# PMOD_PMOD_connector.net
KiCad netlist of a schematic drawn in Altium Designer
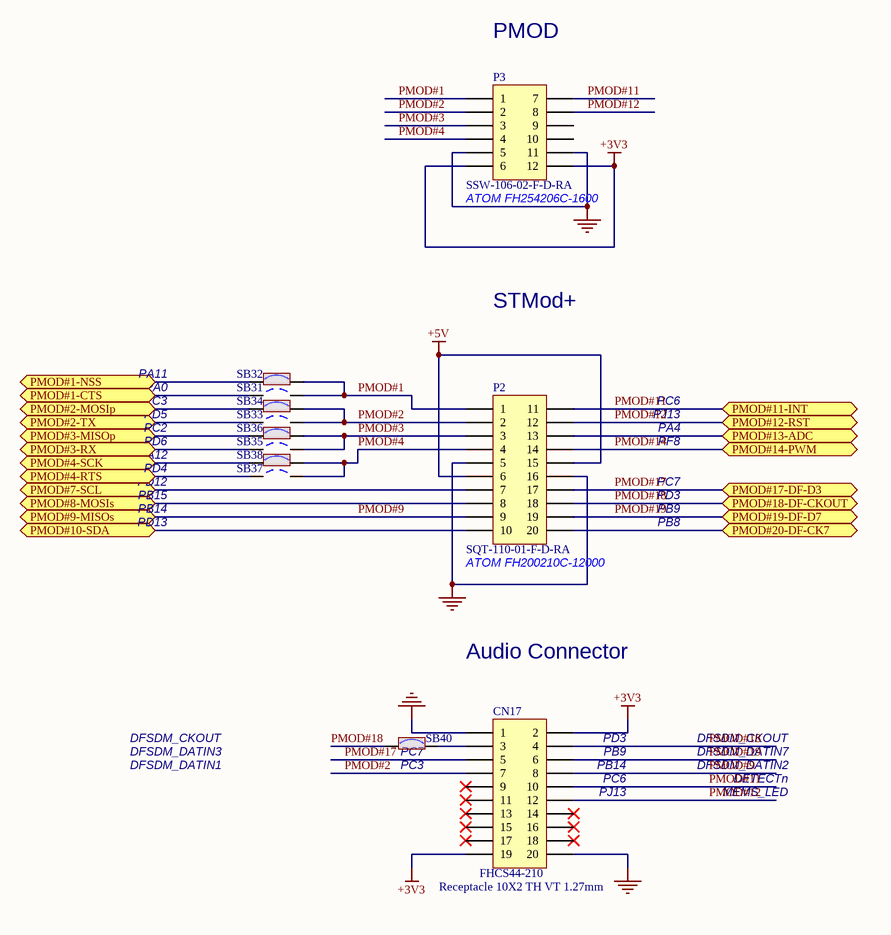
[diagram p0: PMOD_PMOD+ connector .SchDoc]

(export (version "E")
  (design (tool "Eeschema 10.0.6"))
  (components
    (comp (ref "CN17")
      (value "Receptacle 10X2 TH VT 1.27mm")
      (footprint "MODULE_20TH_48X29")
      (description "20 Position Receptacle Connector 0.050\" (1.27mm) Through Hole Vertical Mount")
      (fields (field (name "ORDER_CODE") "FHCS44-210"))
      (libsource (lib "MCD_TEMP_PCH") (part "Receptacle 10X2 TH VT 1.27mm"))
    )
    (comp (ref "P2")
      (value "SQT-110-01-F-D-RA")
      (footprint "SQT-110-01-F-D-RA")
      (description "Header, 10-Pin, Dual row")
      (fields (field (name "PUBLISHER") "Altium Limited"))
      (libsource (lib "Miscellaneous Connectors") (part "Header 10X2A"))
    )
    (comp (ref "P3")
      (value "SSW-106-02-F-D-RA")
      (footprint "SSW-106-02-F-D-RA")
      (description "Header, 6-Pin, Dual row")
      (fields (field (name "PUBLISHER") "Altium Limited"))
      (libsource (lib "Miscellaneous Connectors") (part "Header 6X2A"))
    )
    (comp (ref "SB31")
      (value "Solder Bridge OFF")
      (footprint "SB_0603")
      (libsource (lib "MCD_TOOLS") (part "SB_OFF"))
    )
    (comp (ref "SB32")
      (value "Solder Bridge ON")
      (footprint "SB_0603")
      (libsource (lib "MCD_TOOLS") (part "SB_ON"))
    )
    (comp (ref "SB33")
      (value "Solder Bridge OFF")
      (footprint "SB_0603")
      (libsource (lib "MCD_TOOLS") (part "SB_OFF"))
    )
    (comp (ref "SB34")
      (value "Solder Bridge ON")
      (footprint "SB_0603")
      (libsource (lib "MCD_TOOLS") (part "SB_ON"))
    )
    (comp (ref "SB35")
      (value "Solder Bridge OFF")
      (footprint "SB_0603")
      (libsource (lib "MCD_TOOLS") (part "SB_OFF"))
    )
    (comp (ref "SB36")
      (value "Solder Bridge ON")
      (footprint "SB_0603")
      (libsource (lib "MCD_TOOLS") (part "SB_ON"))
    )
    (comp (ref "SB37")
      (value "Solder Bridge OFF")
      (footprint "SB_0603")
      (libsource (lib "MCD_TOOLS") (part "SB_OFF"))
    )
    (comp (ref "SB38")
      (value "Solder Bridge ON")
      (footprint "SB_0603")
      (libsource (lib "MCD_TOOLS") (part "SB_ON"))
    )
    (comp (ref "SB40")
      (value "Solder Bridge ON")
      (footprint "SB_0603")
      (libsource (lib "MCD_TOOLS") (part "SB_ON"))
    )
  )
  (nets
    (net (code "1") (name "+3V3") (class "Default")
      (node (ref "CN17") (pin "19") (pinfunction "19_19") (pintype "passive"))
      (node (ref "CN17") (pin "2") (pinfunction "2_2") (pintype "passive"))
      (node (ref "P3") (pin "12") (pinfunction "12_12") (pintype "passive"))
      (node (ref "P3") (pin "6") (pinfunction "6_6") (pintype "passive"))
    )
    (net (code "2") (name "+5V") (class "Default")
      (node (ref "P2") (pin "15") (pinfunction "15_15") (pintype "passive"))
      (node (ref "P2") (pin "6") (pinfunction "6_6") (pintype "passive"))
    )
    (net (code "3") (name "/PMOD#1") (class "Default")
      (node (ref "P2") (pin "1") (pinfunction "1_1") (pintype "passive"))
      (node (ref "P3") (pin "1") (pinfunction "1_1") (pintype "passive"))
      (node (ref "SB31") (pin "2") (pinfunction "2_2") (pintype "passive"))
      (node (ref "SB32") (pin "2") (pinfunction "2_2") (pintype "passive"))
    )
    (net (code "4") (name "/PMOD#1-CTS") (class "Default")
      (node (ref "SB31") (pin "1") (pinfunction "1_1") (pintype "passive"))
    )
    (net (code "5") (name "/PMOD#1-NSS") (class "Default")
      (node (ref "SB32") (pin "1") (pinfunction "1_1") (pintype "passive"))
    )
    (net (code "6") (name "/PMOD#2") (class "Default")
      (node (ref "CN17") (pin "7") (pinfunction "7_7") (pintype "passive"))
      (node (ref "P2") (pin "2") (pinfunction "2_2") (pintype "passive"))
      (node (ref "P3") (pin "2") (pinfunction "2_2") (pintype "passive"))
      (node (ref "SB33") (pin "2") (pinfunction "2_2") (pintype "passive"))
      (node (ref "SB34") (pin "2") (pinfunction "2_2") (pintype "passive"))
    )
    (net (code "7") (name "/PMOD#2-MOSIp") (class "Default")
      (node (ref "SB34") (pin "1") (pinfunction "1_1") (pintype "passive"))
    )
    (net (code "8") (name "/PMOD#2-TX") (class "Default")
      (node (ref "SB33") (pin "1") (pinfunction "1_1") (pintype "passive"))
    )
    (net (code "9") (name "/PMOD#3") (class "Default")
      (node (ref "P2") (pin "3") (pinfunction "3_3") (pintype "passive"))
      (node (ref "P3") (pin "3") (pinfunction "3_3") (pintype "passive"))
      (node (ref "SB35") (pin "2") (pinfunction "2_2") (pintype "passive"))
      (node (ref "SB36") (pin "2") (pinfunction "2_2") (pintype "passive"))
    )
    (net (code "10") (name "/PMOD#3-MISOp") (class "Default")
      (node (ref "SB36") (pin "1") (pinfunction "1_1") (pintype "passive"))
    )
    (net (code "11") (name "/PMOD#3-RX") (class "Default")
      (node (ref "SB35") (pin "1") (pinfunction "1_1") (pintype "passive"))
    )
    (net (code "12") (name "/PMOD#4") (class "Default")
      (node (ref "P2") (pin "4") (pinfunction "4_4") (pintype "passive"))
      (node (ref "P3") (pin "4") (pinfunction "4_4") (pintype "passive"))
      (node (ref "SB37") (pin "2") (pinfunction "2_2") (pintype "passive"))
      (node (ref "SB38") (pin "2") (pinfunction "2_2") (pintype "passive"))
    )
    (net (code "13") (name "/PMOD#4-RTS") (class "Default")
      (node (ref "SB37") (pin "1") (pinfunction "1_1") (pintype "passive"))
    )
    (net (code "14") (name "/PMOD#4-SCK") (class "Default")
      (node (ref "SB38") (pin "1") (pinfunction "1_1") (pintype "passive"))
    )
    (net (code "15") (name "/PMOD#7-SCL") (class "Default")
      (node (ref "P2") (pin "7") (pinfunction "7_7") (pintype "passive"))
    )
    (net (code "16") (name "/PMOD#8-MOSIs") (class "Default")
      (node (ref "P2") (pin "8") (pinfunction "8_8") (pintype "passive"))
    )
    (net (code "17") (name "/PMOD#9") (class "Default")
      (node (ref "CN17") (pin "8") (pinfunction "8_8") (pintype "passive"))
      (node (ref "P2") (pin "9") (pinfunction "9_9") (pintype "passive"))
    )
    (net (code "18") (name "/PMOD#10-SDA") (class "Default")
      (node (ref "P2") (pin "10") (pinfunction "10_10") (pintype "passive"))
    )
    (net (code "19") (name "/PMOD#11") (class "Default")
      (node (ref "CN17") (pin "10") (pinfunction "10_10") (pintype "passive"))
      (node (ref "P2") (pin "11") (pinfunction "11_11") (pintype "passive"))
      (node (ref "P3") (pin "7") (pinfunction "7_7") (pintype "passive"))
    )
    (net (code "20") (name "/PMOD#12") (class "Default")
      (node (ref "CN17") (pin "12") (pinfunction "12_12") (pintype "passive"))
      (node (ref "P2") (pin "12") (pinfunction "12_12") (pintype "passive"))
      (node (ref "P3") (pin "8") (pinfunction "8_8") (pintype "passive"))
    )
    (net (code "21") (name "/PMOD#13-ADC") (class "Default")
      (node (ref "P2") (pin "13") (pinfunction "13_13") (pintype "passive"))
    )
    (net (code "22") (name "/PMOD#14") (class "Default")
      (node (ref "P2") (pin "14") (pinfunction "14_14") (pintype "passive"))
    )
    (net (code "23") (name "/PMOD#17") (class "Default")
      (node (ref "CN17") (pin "5") (pinfunction "5_5") (pintype "passive"))
      (node (ref "P2") (pin "17") (pinfunction "17_17") (pintype "passive"))
    )
    (net (code "24") (name "/PMOD#18") (class "Default")
      (node (ref "CN17") (pin "4") (pinfunction "4_4") (pintype "passive"))
      (node (ref "P2") (pin "18") (pinfunction "18_18") (pintype "passive"))
      (node (ref "SB40") (pin "1") (pinfunction "1_1") (pintype "passive"))
    )
    (net (code "25") (name "/PMOD#19") (class "Default")
      (node (ref "CN17") (pin "6") (pinfunction "6_6") (pintype "passive"))
      (node (ref "P2") (pin "19") (pinfunction "19_19") (pintype "passive"))
    )
    (net (code "26") (name "/PMOD#20-DF-CK7") (class "Default")
      (node (ref "P2") (pin "20") (pinfunction "20_20") (pintype "passive"))
    )
    (net (code "27") (name "GND") (class "Default")
      (node (ref "CN17") (pin "1") (pinfunction "1_1") (pintype "passive"))
      (node (ref "CN17") (pin "20") (pinfunction "20_20") (pintype "passive"))
      (node (ref "P2") (pin "16") (pinfunction "16_16") (pintype "passive"))
      (node (ref "P2") (pin "5") (pinfunction "5_5") (pintype "passive"))
      (node (ref "P3") (pin "11") (pinfunction "11_11") (pintype "passive"))
      (node (ref "P3") (pin "5") (pinfunction "5_5") (pintype "passive"))
    )
    (net (code "28") (name "Net-(CN17-Pad3)") (class "Default")
      (node (ref "CN17") (pin "3") (pinfunction "3_3") (pintype "passive"))
      (node (ref "SB40") (pin "2") (pinfunction "2_2") (pintype "passive"))
    )
    (net (code "29") (name "unconnected-(CN17-Pad9)") (class "Default")
      (node (ref "CN17") (pin "9") (pinfunction "9_9") (pintype "passive+no_connect"))
    )
    (net (code "30") (name "unconnected-(CN17-Pad11)") (class "Default")
      (node (ref "CN17") (pin "11") (pinfunction "11_11") (pintype "passive+no_connect"))
    )
    (net (code "31") (name "unconnected-(CN17-Pad13)") (class "Default")
      (node (ref "CN17") (pin "13") (pinfunction "13_13") (pintype "passive+no_connect"))
    )
    (net (code "32") (name "unconnected-(CN17-Pad14)") (class "Default")
      (node (ref "CN17") (pin "14") (pinfunction "14_14") (pintype "passive+no_connect"))
    )
    (net (code "33") (name "unconnected-(CN17-Pad15)") (class "Default")
      (node (ref "CN17") (pin "15") (pinfunction "15_15") (pintype "passive+no_connect"))
    )
    (net (code "34") (name "unconnected-(CN17-Pad16)") (class "Default")
      (node (ref "CN17") (pin "16") (pinfunction "16_16") (pintype "passive+no_connect"))
    )
    (net (code "35") (name "unconnected-(CN17-Pad17)") (class "Default")
      (node (ref "CN17") (pin "17") (pinfunction "17_17") (pintype "passive+no_connect"))
    )
    (net (code "36") (name "unconnected-(CN17-Pad18)") (class "Default")
      (node (ref "CN17") (pin "18") (pinfunction "18_18") (pintype "passive+no_connect"))
    )
    (net (code "37") (name "unconnected-(P3-Pad9)") (class "Default")
      (node (ref "P3") (pin "9") (pinfunction "9_9") (pintype "passive"))
    )
    (net (code "38") (name "unconnected-(P3-Pad10)") (class "Default")
      (node (ref "P3") (pin "10") (pinfunction "10_10") (pintype "passive"))
    )
  )
)
